# OPA2342.net
KiCad netlist of a schematic drawn in Altium Designer
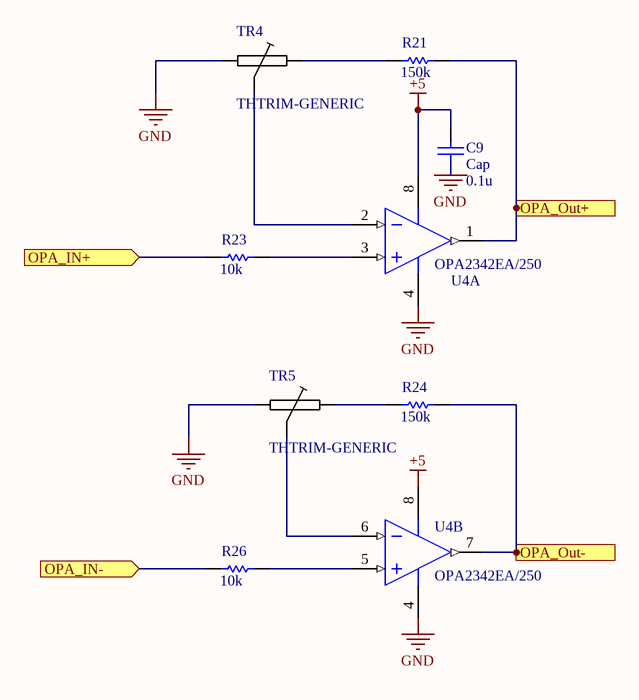
[diagram p0: OPA2342.SchDoc]

(export (version "E")
  (design (tool "Eeschema 10.0.6"))
  (components
    (comp (ref "C9")
      (value "Cap")
      (footprint "C1206")
      (description "Capacitor")
      (fields (field (name "ALTIUM_VALUE") "0.1u") (field (name "PUBLISHER") "Altium Limited"))
      (libsource (lib "Miscellaneous Devices") (part "Cap"))
    )
    (comp (ref "R21")
      (value "150k")
      (footprint "RESC3216X89X51LL25T25")
      (fields (field (name "PART NUMBER") "WSLP1206R0500FEA") (field (name "MANUFACTURER") "Vishay Dale"))
      (libsource (lib "Altium Content Vault") (part "RES"))
    )
    (comp (ref "R23")
      (value "10k")
      (footprint "RESC3216X89X51LL25T25")
      (fields (field (name "PART NUMBER") "WSLP1206R0500FEA") (field (name "MANUFACTURER") "Vishay Dale"))
      (libsource (lib "Altium Content Vault") (part "RES"))
    )
    (comp (ref "R24")
      (value "150k")
      (footprint "RESC3216X89X51LL25T25")
      (fields (field (name "PART NUMBER") "WSLP1206R0500FEA") (field (name "MANUFACTURER") "Vishay Dale"))
      (libsource (lib "Altium Content Vault") (part "RES"))
    )
    (comp (ref "R26")
      (value "10k")
      (footprint "RESC3216X89X51LL25T25")
      (fields (field (name "PART NUMBER") "WSLP1206R0500FEA") (field (name "MANUFACTURER") "Vishay Dale"))
      (libsource (lib "Altium Content Vault") (part "RES"))
    )
    (comp (ref "TR4")
      (value "THTRIM-GENERIC")
      (footprint "TRIMMER-MT")
      (description "TRIMMABLE RESISTOR")
      (libsource (lib "vh_altium_library") (part "THTRIM-GENERIC"))
    )
    (comp (ref "TR5")
      (value "THTRIM-GENERIC")
      (footprint "TRIMMER-MT")
      (description "TRIMMABLE RESISTOR")
      (libsource (lib "vh_altium_library") (part "THTRIM-GENERIC"))
    )
    (comp (ref "U4")
      (value "OPA2342EA/250")
      (footprint "DGK0008A_M")
      (fields (field (name "MANUFACTURER") "Texas Instruments"))
      (libsource (lib "Altium Content Vault") (part "TI-OPA-8_2"))
    )
  )
  (nets
    (net (code "1") (name "+5") (class "Default")
      (node (ref "C9") (pin "1") (pinfunction "1_1") (pintype "passive"))
      (node (ref "U4") (pin "8") (pinfunction "V+_8") (pintype "power_in"))
    )
    (net (code "2") (name "/OPA_IN+") (class "Default")
      (node (ref "R23") (pin "2") (pinfunction "2_2") (pintype "passive"))
    )
    (net (code "3") (name "/OPA_IN-") (class "Default")
      (node (ref "R26") (pin "2") (pinfunction "2_2") (pintype "passive"))
    )
    (net (code "4") (name "/OPA_Out+") (class "Default")
      (node (ref "R21") (pin "1") (pinfunction "1_1") (pintype "passive"))
      (node (ref "U4") (pin "1") (pinfunction "OUT_A_1") (pintype "output"))
    )
    (net (code "5") (name "/OPA_Out-") (class "Default")
      (node (ref "R24") (pin "1") (pinfunction "1_1") (pintype "passive"))
      (node (ref "U4") (pin "7") (pinfunction "OUT_B_7") (pintype "output"))
    )
    (net (code "6") (name "GND") (class "Default")
      (node (ref "C9") (pin "2") (pinfunction "2_2") (pintype "passive"))
      (node (ref "TR4") (pin "1") (pinfunction "1_1") (pintype "passive"))
      (node (ref "TR5") (pin "1") (pinfunction "1_1") (pintype "passive"))
      (node (ref "U4") (pin "4") (pinfunction "V-_4") (pintype "power_in"))
    )
    (net (code "7") (name "Net-(R21-Pad2)") (class "Default")
      (node (ref "R21") (pin "2") (pinfunction "2_2") (pintype "passive"))
      (node (ref "TR4") (pin "2") (pinfunction "2_2") (pintype "passive"))
    )
    (net (code "8") (name "Net-(R24-Pad2)") (class "Default")
      (node (ref "R24") (pin "2") (pinfunction "2_2") (pintype "passive"))
      (node (ref "TR5") (pin "2") (pinfunction "2_2") (pintype "passive"))
    )
    (net (code "9") (name "Net-(U4A-IN_A+)") (class "Default")
      (node (ref "R23") (pin "1") (pinfunction "1_1") (pintype "passive"))
      (node (ref "U4") (pin "3") (pinfunction "IN_A+_3") (pintype "input"))
    )
    (net (code "10") (name "Net-(U4A-IN_A-)") (class "Default")
      (node (ref "TR4") (pin "W") (pinfunction "W_W") (pintype "passive"))
      (node (ref "U4") (pin "2") (pinfunction "IN_A-_2") (pintype "input"))
    )
    (net (code "11") (name "Net-(U4B-IN_B+)") (class "Default")
      (node (ref "R26") (pin "1") (pinfunction "1_1") (pintype "passive"))
      (node (ref "U4") (pin "5") (pinfunction "IN_B+_5") (pintype "input"))
    )
    (net (code "12") (name "Net-(U4B-IN_B-)") (class "Default")
      (node (ref "TR5") (pin "W") (pinfunction "W_W") (pintype "passive"))
      (node (ref "U4") (pin "6") (pinfunction "IN_B-_6") (pintype "input"))
    )
  )
)
